# wifi.net
KiCad netlist of a schematic drawn in Altium Designer
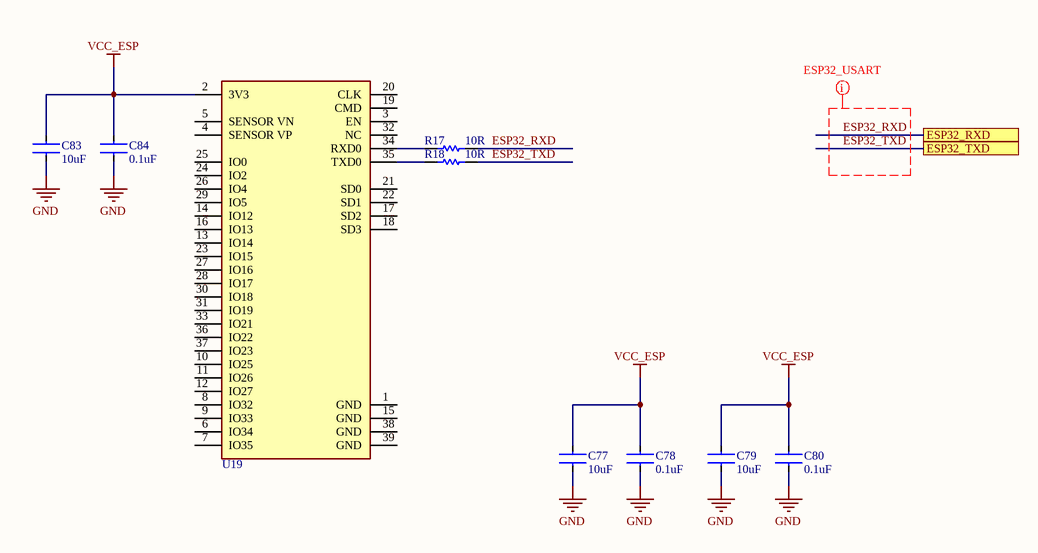
[diagram p0: wifi.SchDoc]

(export (version "E")
  (design (tool "Eeschema 10.0.6"))
  (components
    (comp (ref "C77")
      (value "10uF")
      (footprint "C0402")
      (description "Cap Ceramic 10uF 16V X7R 10% Pad SMD 1206 125°C T/R")
      (fields
        (field (name "MANUFACTURER") "Samsung")
        (field (name "MANUFACTURER PART NUMBER") "CL31B106KOHNNNE")
      )
      (libsource (lib "afra") (part "CL31B106KOHNNNE"))
    )
    (comp (ref "C78")
      (value "0.1uF")
      (footprint "C0402")
      (description "Ceramic capacitor SMD-1206 100nF /50V X7R# K +-10%, Samsung, RoHS")
      (fields
        (field (name "MANUFACTURER") "Samsung")
        (field (name "MANUFACTURER PART NUMBER") "CL31B104KBCNNNC")
      )
      (libsource (lib "afra") (part "CL31B104KBCNNNC"))
    )
    (comp (ref "C79")
      (value "10uF")
      (footprint "C0402")
      (description "Cap Ceramic 10uF 16V X7R 10% Pad SMD 1206 125°C T/R")
      (fields
        (field (name "MANUFACTURER") "Samsung")
        (field (name "MANUFACTURER PART NUMBER") "CL31B106KOHNNNE")
      )
      (libsource (lib "afra") (part "CL31B106KOHNNNE"))
    )
    (comp (ref "C80")
      (value "0.1uF")
      (footprint "C0402")
      (description "Ceramic capacitor SMD-1206 100nF /50V X7R# K +-10%, Samsung, RoHS")
      (fields
        (field (name "MANUFACTURER") "Samsung")
        (field (name "MANUFACTURER PART NUMBER") "CL31B104KBCNNNC")
      )
      (libsource (lib "afra") (part "CL31B104KBCNNNC"))
    )
    (comp (ref "C83")
      (value "10uF")
      (footprint "C0402")
      (description "Cap Ceramic 10uF 16V X7R 10% Pad SMD 1206 125°C T/R")
      (fields
        (field (name "MANUFACTURER") "Samsung")
        (field (name "MANUFACTURER PART NUMBER") "CL31B106KOHNNNE")
      )
      (libsource (lib "afra") (part "CL31B106KOHNNNE"))
    )
    (comp (ref "C84")
      (value "0.1uF")
      (footprint "C0402")
      (description "Ceramic capacitor SMD-1206 100nF /50V X7R# K +-10%, Samsung, RoHS")
      (fields
        (field (name "MANUFACTURER") "Samsung")
        (field (name "MANUFACTURER PART NUMBER") "CL31B104KBCNNNC")
      )
      (libsource (lib "afra") (part "CL31B104KBCNNNC"))
    )
    (comp (ref "R17")
      (value "10R")
      (footprint "R0402")
      (description "Res Thick Film 1206 10 Ohm 1% 0.25W(1/4W) +/-200ppm/ßC Epoxy SMD T/R")
      (fields
        (field (name "MANUFACTURER") "Yageo")
        (field (name "MANUFACTURER PART NUMBER") "RC1206FR-0710RL")
      )
      (libsource (lib "afra") (part "RC1206FR-0710RL"))
    )
    (comp (ref "R18")
      (value "10R")
      (footprint "R0402")
      (description "Res Thick Film 1206 10 Ohm 1% 0.25W(1/4W) +/-200ppm/ßC Epoxy SMD T/R")
      (fields
        (field (name "MANUFACTURER") "Yageo")
        (field (name "MANUFACTURER PART NUMBER") "RC1206FR-0710RL")
      )
      (libsource (lib "afra") (part "RC1206FR-0710RL"))
    )
    (comp (ref "U19")
      (value "BLE/WIFI Module")
      (footprint "Espressif_ESP-WROOM-32_0")
      (description "IC SPRESSIF ESP32 BLUETOOTH WIFI Module")
      (fields (field (name "MANUFACTURER") "Espressif") (field (name "MOUSER PART NUMBER") "485-3320"))
      (libsource (lib "afra") (part "IC_Espressif_ESP-WROOM-32_eec"))
    )
  )
  (nets
    (net (code "1") (name "/ESP32_RXD") (class "Default")
      (node (ref "R17") (pin "2") (pinfunction "2_2") (pintype "passive"))
    )
    (net (code "2") (name "/ESP32_TXD") (class "Default")
      (node (ref "R18") (pin "2") (pinfunction "2_2") (pintype "passive"))
    )
    (net (code "3") (name "GND") (class "Default")
      (node (ref "C77") (pin "2") (pinfunction "2_2") (pintype "passive"))
      (node (ref "C78") (pin "2") (pinfunction "2_2") (pintype "passive"))
      (node (ref "C79") (pin "2") (pinfunction "2_2") (pintype "passive"))
      (node (ref "C80") (pin "2") (pinfunction "2_2") (pintype "passive"))
      (node (ref "C83") (pin "2") (pinfunction "2_2") (pintype "passive"))
      (node (ref "C84") (pin "2") (pinfunction "2_2") (pintype "passive"))
    )
    (net (code "4") (name "Net-(U19-RXD0)") (class "Default")
      (node (ref "R17") (pin "1") (pinfunction "1_1") (pintype "passive"))
      (node (ref "U19") (pin "34") (pinfunction "RXD0_34") (pintype "passive"))
    )
    (net (code "5") (name "Net-(U19-TXD0)") (class "Default")
      (node (ref "R18") (pin "1") (pinfunction "1_1") (pintype "passive"))
      (node (ref "U19") (pin "35") (pinfunction "TXD0_35") (pintype "passive"))
    )
    (net (code "6") (name "VCC_ESP") (class "Default")
      (node (ref "C77") (pin "1") (pinfunction "1_1") (pintype "passive"))
      (node (ref "C78") (pin "1") (pinfunction "1_1") (pintype "passive"))
      (node (ref "C79") (pin "1") (pinfunction "1_1") (pintype "passive"))
      (node (ref "C80") (pin "1") (pinfunction "1_1") (pintype "passive"))
      (node (ref "C83") (pin "1") (pinfunction "1_1") (pintype "passive"))
      (node (ref "C84") (pin "1") (pinfunction "1_1") (pintype "passive"))
      (node (ref "U19") (pin "2") (pinfunction "3V3_2") (pintype "passive"))
    )
    (net (code "7") (name "unconnected-(U19-CLK-Pad20)") (class "Default")
      (node (ref "U19") (pin "20") (pinfunction "CLK_20") (pintype "passive"))
    )
    (net (code "8") (name "unconnected-(U19-CMD-Pad19)") (class "Default")
      (node (ref "U19") (pin "19") (pinfunction "CMD_19") (pintype "passive"))
    )
    (net (code "9") (name "unconnected-(U19-EN-Pad3)") (class "Default")
      (node (ref "U19") (pin "3") (pinfunction "EN_3") (pintype "passive"))
    )
    (net (code "10") (name "unconnected-(U19-GND-Pad1)") (class "Default")
      (node (ref "U19") (pin "1") (pinfunction "GND_1") (pintype "passive"))
    )
    (net (code "11") (name "unconnected-(U19-GND-Pad15)") (class "Default")
      (node (ref "U19") (pin "15") (pinfunction "GND_15") (pintype "passive"))
    )
    (net (code "12") (name "unconnected-(U19-GND-Pad38)") (class "Default")
      (node (ref "U19") (pin "38") (pinfunction "GND_38") (pintype "passive"))
    )
    (net (code "13") (name "unconnected-(U19-GND-Pad39)") (class "Default")
      (node (ref "U19") (pin "39") (pinfunction "GND_39") (pintype "passive"))
    )
    (net (code "14") (name "unconnected-(U19-IO0-Pad25)") (class "Default")
      (node (ref "U19") (pin "25") (pinfunction "IO0_25") (pintype "passive"))
    )
    (net (code "15") (name "unconnected-(U19-IO2-Pad24)") (class "Default")
      (node (ref "U19") (pin "24") (pinfunction "IO2_24") (pintype "passive"))
    )
    (net (code "16") (name "unconnected-(U19-IO4-Pad26)") (class "Default")
      (node (ref "U19") (pin "26") (pinfunction "IO4_26") (pintype "passive"))
    )
    (net (code "17") (name "unconnected-(U19-IO5-Pad29)") (class "Default")
      (node (ref "U19") (pin "29") (pinfunction "IO5_29") (pintype "passive"))
    )
    (net (code "18") (name "unconnected-(U19-IO12-Pad14)") (class "Default")
      (node (ref "U19") (pin "14") (pinfunction "IO12_14") (pintype "passive"))
    )
    (net (code "19") (name "unconnected-(U19-IO13-Pad16)") (class "Default")
      (node (ref "U19") (pin "16") (pinfunction "IO13_16") (pintype "passive"))
    )
    (net (code "20") (name "unconnected-(U19-IO14-Pad13)") (class "Default")
      (node (ref "U19") (pin "13") (pinfunction "IO14_13") (pintype "passive"))
    )
    (net (code "21") (name "unconnected-(U19-IO15-Pad23)") (class "Default")
      (node (ref "U19") (pin "23") (pinfunction "IO15_23") (pintype "passive"))
    )
    (net (code "22") (name "unconnected-(U19-IO16-Pad27)") (class "Default")
      (node (ref "U19") (pin "27") (pinfunction "IO16_27") (pintype "passive"))
    )
    (net (code "23") (name "unconnected-(U19-IO17-Pad28)") (class "Default")
      (node (ref "U19") (pin "28") (pinfunction "IO17_28") (pintype "passive"))
    )
    (net (code "24") (name "unconnected-(U19-IO18-Pad30)") (class "Default")
      (node (ref "U19") (pin "30") (pinfunction "IO18_30") (pintype "passive"))
    )
    (net (code "25") (name "unconnected-(U19-IO19-Pad31)") (class "Default")
      (node (ref "U19") (pin "31") (pinfunction "IO19_31") (pintype "passive"))
    )
    (net (code "26") (name "unconnected-(U19-IO21-Pad33)") (class "Default")
      (node (ref "U19") (pin "33") (pinfunction "IO21_33") (pintype "passive"))
    )
    (net (code "27") (name "unconnected-(U19-IO22-Pad36)") (class "Default")
      (node (ref "U19") (pin "36") (pinfunction "IO22_36") (pintype "passive"))
    )
    (net (code "28") (name "unconnected-(U19-IO23-Pad37)") (class "Default")
      (node (ref "U19") (pin "37") (pinfunction "IO23_37") (pintype "passive"))
    )
    (net (code "29") (name "unconnected-(U19-IO25-Pad10)") (class "Default")
      (node (ref "U19") (pin "10") (pinfunction "IO25_10") (pintype "passive"))
    )
    (net (code "30") (name "unconnected-(U19-IO26-Pad11)") (class "Default")
      (node (ref "U19") (pin "11") (pinfunction "IO26_11") (pintype "passive"))
    )
    (net (code "31") (name "unconnected-(U19-IO27-Pad12)") (class "Default")
      (node (ref "U19") (pin "12") (pinfunction "IO27_12") (pintype "passive"))
    )
    (net (code "32") (name "unconnected-(U19-IO32-Pad8)") (class "Default")
      (node (ref "U19") (pin "8") (pinfunction "IO32_8") (pintype "passive"))
    )
    (net (code "33") (name "unconnected-(U19-IO33-Pad9)") (class "Default")
      (node (ref "U19") (pin "9") (pinfunction "IO33_9") (pintype "passive"))
    )
    (net (code "34") (name "unconnected-(U19-IO34-Pad6)") (class "Default")
      (node (ref "U19") (pin "6") (pinfunction "IO34_6") (pintype "passive"))
    )
    (net (code "35") (name "unconnected-(U19-IO35-Pad7)") (class "Default")
      (node (ref "U19") (pin "7") (pinfunction "IO35_7") (pintype "passive"))
    )
    (net (code "36") (name "unconnected-(U19-NC-Pad32)") (class "Default")
      (node (ref "U19") (pin "32") (pinfunction "NC_32") (pintype "passive"))
    )
    (net (code "37") (name "unconnected-(U19-SD0-Pad21)") (class "Default")
      (node (ref "U19") (pin "21") (pinfunction "SD0_21") (pintype "passive"))
    )
    (net (code "38") (name "unconnected-(U19-SD1-Pad22)") (class "Default")
      (node (ref "U19") (pin "22") (pinfunction "SD1_22") (pintype "passive"))
    )
    (net (code "39") (name "unconnected-(U19-SD2-Pad17)") (class "Default")
      (node (ref "U19") (pin "17") (pinfunction "SD2_17") (pintype "passive"))
    )
    (net (code "40") (name "unconnected-(U19-SD3-Pad18)") (class "Default")
      (node (ref "U19") (pin "18") (pinfunction "SD3_18") (pintype "passive"))
    )
    (net (code "41") (name "unconnected-(U19-SENSOR_VN-Pad5)") (class "Default")
      (node (ref "U19") (pin "5") (pinfunction "SENSOR_VN_5") (pintype "passive"))
    )
    (net (code "42") (name "unconnected-(U19-SENSOR_VP-Pad4)") (class "Default")
      (node (ref "U19") (pin "4") (pinfunction "SENSOR_VP_4") (pintype "passive"))
    )
  )
)
